# PWM_CON_PowerSupply.net
KiCad netlist of a schematic drawn in Altium Designer
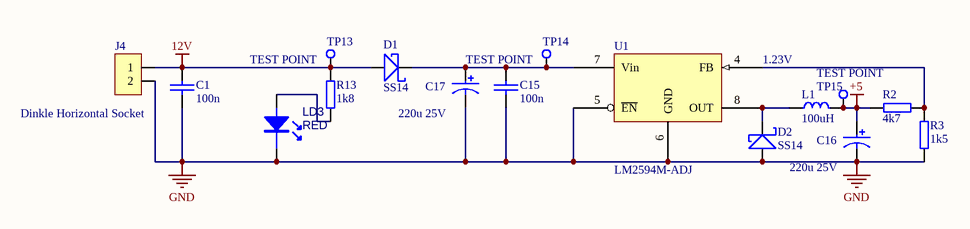
[diagram p0: PWM_CON_PowerSupply.SchDoc]

(export (version "E")
  (design (tool "Eeschema 10.0.6"))
  (components
    (comp (ref "C1")
      (value "100n")
      (footprint "0603")
      (fields (field (name "PARTNO") "R8835"))
      (libsource (lib "*") (part "CAP"))
    )
    (comp (ref "C15")
      (value "100n")
      (footprint "0603")
      (fields (field (name "PARTNO") "R8835"))
      (libsource (lib "*") (part "CAP"))
    )
    (comp (ref "C16")
      (value "220u 25V")
      (footprint "RB.15/.32")
      (fields (field (name "PARTNO") "R5144"))
      (libsource (lib "DEVICE") (part "CAPACITOR POL-S"))
    )
    (comp (ref "C17")
      (value "220u 25V")
      (footprint "RB.15/.32")
      (fields (field (name "PARTNO") "R5144"))
      (libsource (lib "DEVICE") (part "CAPACITOR POL-S"))
    )
    (comp (ref "D1")
      (value "SS14")
      (footprint "DO-214AC")
      (description "SCHOTTKY , 1A, 40V")
      (fields (field (name "PARTNO") "4085159"))
      (libsource (lib "DEVICE") (part "DIODE SCHOTTKY-S"))
    )
    (comp (ref "D2")
      (value "SS14")
      (footprint "DO-214AC")
      (description "SCHOTTKY , 1A, 40V")
      (fields (field (name "PARTNO") "4085159"))
      (libsource (lib "DEVICE") (part "DIODE SCHOTTKY-S"))
    )
    (comp (ref "J4")
      (value "Dinkle Horizontal Socket")
      (footprint "WEID2R")
      (fields (field (name "PARTNO") "P2552"))
      (libsource (lib "DEVICE") (part "CON2"))
    )
    (comp (ref "L1")
      (value "100uH")
      (footprint "INDUCTOR6B")
      (description "0.5A Inductor")
      (fields (field (name "PARTNO") "L6222"))
      (libsource (lib "*") (part "INDUCTOR6"))
    )
    (comp (ref "LD3")
      (value "RED")
      (footprint "0805DIODE")
      (fields (field (name "PARTNO") "Y1107"))
      (libsource (lib "*") (part "LED"))
    )
    (comp (ref "R2")
      (value "4k7")
      (footprint "0603")
      (description "1% Resistor")
      (fields (field (name "PARTNO") "R1644"))
      (libsource (lib "DEVICE") (part "RES8"))
    )
    (comp (ref "R3")
      (value "1k5")
      (footprint "0603")
      (description "1% Resistor")
      (fields (field (name "PARTNO") "R1608"))
      (libsource (lib "DEVICE") (part "RES8"))
    )
    (comp (ref "R13")
      (value "1k8")
      (footprint "0603")
      (description "1% Resistor")
      (fields (field (name "PARTNO") "R1614"))
      (libsource (lib "DEVICE") (part "RES8"))
    )
    (comp (ref "TP13")
      (value "TEST POINT")
      (footprint "TEST POINT")
      (description "Probe compatible test point")
      (libsource (lib "DEVICE") (part "TEST POINT"))
    )
    (comp (ref "TP14")
      (value "TEST POINT")
      (footprint "TEST POINT")
      (description "Probe compatible test point")
      (libsource (lib "DEVICE") (part "TEST POINT"))
    )
    (comp (ref "TP15")
      (value "TEST POINT")
      (footprint "TEST POINT")
      (description "Probe compatible test point")
      (libsource (lib "DEVICE") (part "TEST POINT"))
    )
    (comp (ref "U1")
      (value "LM2594M-ADJ")
      (footprint "M08A_N")
      (description "SMPS 0.5A")
      (fields (field (name "PARTNO") "9494332"))
      (libsource (lib "NS-EXTRA") (part "LM2594"))
    )
  )
  (nets
    (net (code "1") (name "+5") (class "Default")
      (node (ref "C16") (pin "1") (pinfunction "1_1") (pintype "passive"))
      (node (ref "L1") (pin "2") (pintype "passive"))
      (node (ref "R2") (pin "1") (pintype "passive"))
      (node (ref "TP15") (pin "1") (pinfunction "1_1") (pintype "passive"))
    )
    (net (code "2") (name "12V") (class "Default")
      (node (ref "C1") (pin "2") (pintype "passive"))
      (node (ref "D1") (pin "A") (pinfunction "A_A") (pintype "passive"))
      (node (ref "J4") (pin "1") (pinfunction "1_1") (pintype "passive"))
      (node (ref "R13") (pin "1") (pintype "passive"))
      (node (ref "TP13") (pin "1") (pinfunction "1_1") (pintype "passive"))
    )
    (net (code "3") (name "GND") (class "Default")
      (node (ref "C1") (pin "1") (pintype "passive"))
      (node (ref "C15") (pin "1") (pintype "passive"))
      (node (ref "C16") (pin "2") (pinfunction "2_2") (pintype "passive"))
      (node (ref "C17") (pin "2") (pinfunction "2_2") (pintype "passive"))
      (node (ref "D2") (pin "A") (pinfunction "A_A") (pintype "passive"))
      (node (ref "J4") (pin "2") (pinfunction "2_2") (pintype "passive"))
      (node (ref "LD3") (pin "K") (pintype "passive"))
      (node (ref "R3") (pin "2") (pintype "passive"))
      (node (ref "U1") (pin "5") (pinfunction "~{EN}_5") (pintype "passive"))
      (node (ref "U1") (pin "6") (pinfunction "GND_6") (pintype "power_in"))
    )
    (net (code "4") (name "Net-(LD3-PadA)") (class "Default")
      (node (ref "LD3") (pin "A") (pintype "passive"))
      (node (ref "R13") (pin "2") (pintype "passive"))
    )
    (net (code "5") (name "Net-(U1-FB)") (class "Default")
      (node (ref "R2") (pin "2") (pintype "passive"))
      (node (ref "R3") (pin "1") (pintype "passive"))
      (node (ref "U1") (pin "4") (pinfunction "FB_4") (pintype "input"))
    )
    (net (code "6") (name "Net-(U1-OUT)") (class "Default")
      (node (ref "D2") (pin "K") (pinfunction "K_K") (pintype "passive"))
      (node (ref "L1") (pin "1") (pintype "passive"))
      (node (ref "U1") (pin "8") (pinfunction "OUT_8") (pintype "power_in"))
    )
    (net (code "7") (name "Net-(U1-Vin)") (class "Default")
      (node (ref "C15") (pin "2") (pintype "passive"))
      (node (ref "C17") (pin "1") (pinfunction "1_1") (pintype "passive"))
      (node (ref "D1") (pin "K") (pinfunction "K_K") (pintype "passive"))
      (node (ref "TP14") (pin "1") (pinfunction "1_1") (pintype "passive"))
      (node (ref "U1") (pin "7") (pinfunction "Vin_7") (pintype "passive"))
    )
  )
)
